# Sheet1.net
KiCad netlist of a schematic drawn in Altium Designer
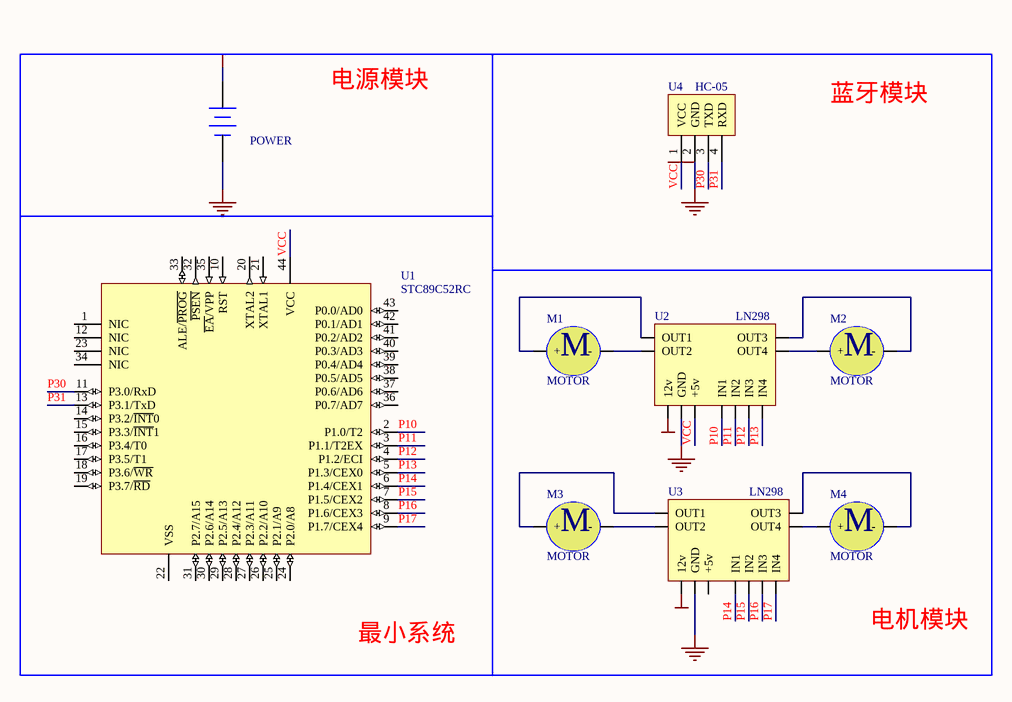
[diagram p0: Sheet1.SchDoc]

(export (version "E")
  (design (tool "Eeschema 10.0.6"))
  (components
    (comp (ref "M1") (value "MOTOR") (libsource (lib "MySchlib1") (part "MOTOR")))
    (comp (ref "M2") (value "MOTOR") (libsource (lib "MySchlib1") (part "MOTOR")))
    (comp (ref "M3") (value "MOTOR") (libsource (lib "MySchlib1") (part "MOTOR")))
    (comp (ref "M4") (value "MOTOR") (libsource (lib "MySchlib1") (part "MOTOR")))
    (comp (ref "POWER") (value "~") (footprint "NKBATTERY") (libsource (lib "*") (part "BATTERY")))
    (comp (ref "U1")
      (value "STC89C52RC")
      (footprint "SOT187-2")
      (description "80C51 8-Bit Flash Microcontroller Family, 8 kB ISP/IAP Flash with 512 B RAM.")
      (fields (field (name "PUBLISHER") "Altium Limited"))
      (libsource (lib "Philips Microcontroller 8-Bit") (part "P89C51RA2BA/01"))
    )
    (comp (ref "U2") (value "LN298") (libsource (lib "MySchlib1") (part "LN298")))
    (comp (ref "U3") (value "LN298") (libsource (lib "*") (part "LN298")))
    (comp (ref "U4") (value "HC-05") (libsource (lib "*") (part "HC-05")))
  )
  (nets
    (net (code "1") (name "/P10") (class "Default")
      (node (ref "U1") (pin "2") (pinfunction "P1.0/T2_2") (pintype "bidirectional"))
      (node (ref "U2") (pin "7") (pinfunction "IN1_7") (pintype "passive"))
    )
    (net (code "2") (name "/P11") (class "Default")
      (node (ref "U1") (pin "3") (pinfunction "P1.1/T2EX_3") (pintype "bidirectional"))
      (node (ref "U2") (pin "8") (pinfunction "IN2_8") (pintype "passive"))
    )
    (net (code "3") (name "/P12") (class "Default")
      (node (ref "U1") (pin "4") (pinfunction "P1.2/ECI_4") (pintype "bidirectional"))
      (node (ref "U2") (pin "9") (pinfunction "IN3_9") (pintype "passive"))
    )
    (net (code "4") (name "/P13") (class "Default")
      (node (ref "U1") (pin "5") (pinfunction "P1.3/CEX0_5") (pintype "bidirectional"))
      (node (ref "U2") (pin "10") (pinfunction "IN4_10") (pintype "passive"))
    )
    (net (code "5") (name "/P14") (class "Default")
      (node (ref "U1") (pin "6") (pinfunction "P1.4/CEX1_6") (pintype "bidirectional"))
      (node (ref "U3") (pin "7") (pinfunction "IN1_7") (pintype "passive"))
    )
    (net (code "6") (name "/P15") (class "Default")
      (node (ref "U1") (pin "7") (pinfunction "P1.5/CEX2_7") (pintype "bidirectional"))
      (node (ref "U3") (pin "8") (pinfunction "IN2_8") (pintype "passive"))
    )
    (net (code "7") (name "/P16") (class "Default")
      (node (ref "U1") (pin "8") (pinfunction "P1.6/CEX3_8") (pintype "bidirectional"))
      (node (ref "U3") (pin "9") (pinfunction "IN3_9") (pintype "passive"))
    )
    (net (code "8") (name "/P17") (class "Default")
      (node (ref "U1") (pin "9") (pinfunction "P1.7/CEX4_9") (pintype "bidirectional"))
      (node (ref "U3") (pin "10") (pinfunction "IN4_10") (pintype "passive"))
    )
    (net (code "9") (name "/P30") (class "Default")
      (node (ref "U1") (pin "11") (pinfunction "P3.0/RxD_11") (pintype "bidirectional"))
      (node (ref "U4") (pin "3") (pinfunction "TXD_3") (pintype "passive"))
    )
    (net (code "10") (name "/P31") (class "Default")
      (node (ref "U1") (pin "13") (pinfunction "P3.1/TxD_13") (pintype "bidirectional"))
      (node (ref "U4") (pin "4") (pinfunction "RXD_4") (pintype "passive"))
    )
    (net (code "11") (name "/VCC") (class "Default")
      (node (ref "U1") (pin "44") (pinfunction "VCC_44") (pintype "power_in"))
      (node (ref "U2") (pin "6") (pinfunction "+5v_6") (pintype "passive"))
      (node (ref "U4") (pin "1") (pinfunction "VCC_1") (pintype "passive"))
    )
    (net (code "12") (name "12V") (class "Default")
      (node (ref "POWER") (pin "1") (pinfunction "+_1") (pintype "passive"))
      (node (ref "U2") (pin "4") (pinfunction "12v_4") (pintype "passive"))
      (node (ref "U3") (pin "4") (pinfunction "12v_4") (pintype "passive"))
    )
    (net (code "13") (name "GND") (class "Default")
      (node (ref "U2") (pin "5") (pinfunction "GND_5") (pintype "passive"))
      (node (ref "U3") (pin "5") (pinfunction "GND_5") (pintype "passive"))
      (node (ref "U4") (pin "2") (pinfunction "GND_2") (pintype "passive"))
    )
    (net (code "14") (name "Net-(M1-+)") (class "Default")
      (node (ref "M1") (pin "0") (pinfunction "+_0") (pintype "passive"))
      (node (ref "U2") (pin "0") (pinfunction "OUT1_0") (pintype "passive"))
    )
    (net (code "15") (name "Net-(M1--)") (class "Default")
      (node (ref "M1") (pin "1") (pinfunction "-_1") (pintype "passive"))
      (node (ref "U2") (pin "1") (pinfunction "OUT2_1") (pintype "passive"))
    )
    (net (code "16") (name "Net-(M2-+)") (class "Default")
      (node (ref "M2") (pin "0") (pinfunction "+_0") (pintype "passive"))
      (node (ref "U2") (pin "3") (pinfunction "OUT4_3") (pintype "passive"))
    )
    (net (code "17") (name "Net-(M2--)") (class "Default")
      (node (ref "M2") (pin "1") (pinfunction "-_1") (pintype "passive"))
      (node (ref "U2") (pin "2") (pinfunction "OUT3_2") (pintype "passive"))
    )
    (net (code "18") (name "Net-(M3-+)") (class "Default")
      (node (ref "M3") (pin "0") (pinfunction "+_0") (pintype "passive"))
      (node (ref "U3") (pin "0") (pinfunction "OUT1_0") (pintype "passive"))
    )
    (net (code "19") (name "Net-(M3--)") (class "Default")
      (node (ref "M3") (pin "1") (pinfunction "-_1") (pintype "passive"))
      (node (ref "U3") (pin "1") (pinfunction "OUT2_1") (pintype "passive"))
    )
    (net (code "20") (name "Net-(M4-+)") (class "Default")
      (node (ref "M4") (pin "0") (pinfunction "+_0") (pintype "passive"))
      (node (ref "U3") (pin "3") (pinfunction "OUT4_3") (pintype "passive"))
    )
    (net (code "21") (name "Net-(M4--)") (class "Default")
      (node (ref "M4") (pin "1") (pinfunction "-_1") (pintype "passive"))
      (node (ref "U3") (pin "2") (pinfunction "OUT3_2") (pintype "passive"))
    )
    (net (code "22") (name "unconnected-(POWER-+-Pad2)") (class "Default")
      (node (ref "POWER") (pin "2") (pinfunction "+_2") (pintype "passive"))
    )
    (net (code "23") (name "unconnected-(U1-ALE{slash}~{PROG}-Pad33)") (class "Default")
      (node (ref "U1") (pin "33") (pinfunction "ALE/~{PROG}_33") (pintype "bidirectional"))
    )
    (net (code "24") (name "unconnected-(U1-NIC-Pad1)") (class "Default")
      (node (ref "U1") (pin "1") (pinfunction "NIC_1") (pintype "passive"))
    )
    (net (code "25") (name "unconnected-(U1-NIC-Pad12)") (class "Default")
      (node (ref "U1") (pin "12") (pinfunction "NIC_12") (pintype "passive"))
    )
    (net (code "26") (name "unconnected-(U1-NIC-Pad23)") (class "Default")
      (node (ref "U1") (pin "23") (pinfunction "NIC_23") (pintype "passive"))
    )
    (net (code "27") (name "unconnected-(U1-NIC-Pad34)") (class "Default")
      (node (ref "U1") (pin "34") (pinfunction "NIC_34") (pintype "passive"))
    )
    (net (code "28") (name "unconnected-(U1-P0.0{slash}AD0-Pad43)") (class "Default")
      (node (ref "U1") (pin "43") (pinfunction "P0.0/AD0_43") (pintype "bidirectional"))
    )
    (net (code "29") (name "unconnected-(U1-P0.1{slash}AD1-Pad42)") (class "Default")
      (node (ref "U1") (pin "42") (pinfunction "P0.1/AD1_42") (pintype "bidirectional"))
    )
    (net (code "30") (name "unconnected-(U1-P0.2{slash}AD2-Pad41)") (class "Default")
      (node (ref "U1") (pin "41") (pinfunction "P0.2/AD2_41") (pintype "bidirectional"))
    )
    (net (code "31") (name "unconnected-(U1-P0.3{slash}AD3-Pad40)") (class "Default")
      (node (ref "U1") (pin "40") (pinfunction "P0.3/AD3_40") (pintype "bidirectional"))
    )
    (net (code "32") (name "unconnected-(U1-P0.4{slash}AD4-Pad39)") (class "Default")
      (node (ref "U1") (pin "39") (pinfunction "P0.4/AD4_39") (pintype "bidirectional"))
    )
    (net (code "33") (name "unconnected-(U1-P0.5{slash}AD5-Pad38)") (class "Default")
      (node (ref "U1") (pin "38") (pinfunction "P0.5/AD5_38") (pintype "bidirectional"))
    )
    (net (code "34") (name "unconnected-(U1-P0.6{slash}AD6-Pad37)") (class "Default")
      (node (ref "U1") (pin "37") (pinfunction "P0.6/AD6_37") (pintype "bidirectional"))
    )
    (net (code "35") (name "unconnected-(U1-P0.7{slash}AD7-Pad36)") (class "Default")
      (node (ref "U1") (pin "36") (pinfunction "P0.7/AD7_36") (pintype "bidirectional"))
    )
    (net (code "36") (name "unconnected-(U1-P2.0{slash}A8-Pad24)") (class "Default")
      (node (ref "U1") (pin "24") (pinfunction "P2.0/A8_24") (pintype "bidirectional"))
    )
    (net (code "37") (name "unconnected-(U1-P2.1{slash}A9-Pad25)") (class "Default")
      (node (ref "U1") (pin "25") (pinfunction "P2.1/A9_25") (pintype "bidirectional"))
    )
    (net (code "38") (name "unconnected-(U1-P2.2{slash}A10-Pad26)") (class "Default")
      (node (ref "U1") (pin "26") (pinfunction "P2.2/A10_26") (pintype "bidirectional"))
    )
    (net (code "39") (name "unconnected-(U1-P2.3{slash}A11-Pad27)") (class "Default")
      (node (ref "U1") (pin "27") (pinfunction "P2.3/A11_27") (pintype "bidirectional"))
    )
    (net (code "40") (name "unconnected-(U1-P2.4{slash}A12-Pad28)") (class "Default")
      (node (ref "U1") (pin "28") (pinfunction "P2.4/A12_28") (pintype "bidirectional"))
    )
    (net (code "41") (name "unconnected-(U1-P2.5{slash}A13-Pad29)") (class "Default")
      (node (ref "U1") (pin "29") (pinfunction "P2.5/A13_29") (pintype "bidirectional"))
    )
    (net (code "42") (name "unconnected-(U1-P2.6{slash}A14-Pad30)") (class "Default")
      (node (ref "U1") (pin "30") (pinfunction "P2.6/A14_30") (pintype "bidirectional"))
    )
    (net (code "43") (name "unconnected-(U1-P2.7{slash}A15-Pad31)") (class "Default")
      (node (ref "U1") (pin "31") (pinfunction "P2.7/A15_31") (pintype "bidirectional"))
    )
    (net (code "44") (name "unconnected-(U1-P3.2{slash}~{INT}0-Pad14)") (class "Default")
      (node (ref "U1") (pin "14") (pinfunction "P3.2/~{INT}0_14") (pintype "bidirectional"))
    )
    (net (code "45") (name "unconnected-(U1-P3.3{slash}~{INT}1-Pad15)") (class "Default")
      (node (ref "U1") (pin "15") (pinfunction "P3.3/~{INT}1_15") (pintype "bidirectional"))
    )
    (net (code "46") (name "unconnected-(U1-P3.4{slash}T0-Pad16)") (class "Default")
      (node (ref "U1") (pin "16") (pinfunction "P3.4/T0_16") (pintype "bidirectional"))
    )
    (net (code "47") (name "unconnected-(U1-P3.5{slash}T1-Pad17)") (class "Default")
      (node (ref "U1") (pin "17") (pinfunction "P3.5/T1_17") (pintype "bidirectional"))
    )
    (net (code "48") (name "unconnected-(U1-P3.6{slash}~{WR}-Pad18)") (class "Default")
      (node (ref "U1") (pin "18") (pinfunction "P3.6/~{WR}_18") (pintype "bidirectional"))
    )
    (net (code "49") (name "unconnected-(U1-P3.7{slash}~{RD}-Pad19)") (class "Default")
      (node (ref "U1") (pin "19") (pinfunction "P3.7/~{RD}_19") (pintype "bidirectional"))
    )
    (net (code "50") (name "unconnected-(U1-RST-Pad10)") (class "Default")
      (node (ref "U1") (pin "10") (pinfunction "RST_10") (pintype "input"))
    )
    (net (code "51") (name "unconnected-(U1-VSS-Pad22)") (class "Default")
      (node (ref "U1") (pin "22") (pinfunction "VSS_22") (pintype "power_in"))
    )
    (net (code "52") (name "unconnected-(U1-XTAL1-Pad21)") (class "Default")
      (node (ref "U1") (pin "21") (pinfunction "XTAL1_21") (pintype "input"))
    )
    (net (code "53") (name "unconnected-(U1-XTAL2-Pad20)") (class "Default")
      (node (ref "U1") (pin "20") (pinfunction "XTAL2_20") (pintype "output"))
    )
    (net (code "54") (name "unconnected-(U1-~{EA}{slash}VPP-Pad35)") (class "Default")
      (node (ref "U1") (pin "35") (pinfunction "~{EA}/VPP_35") (pintype "input"))
    )
    (net (code "55") (name "unconnected-(U1-~{PSEN}-Pad32)") (class "Default")
      (node (ref "U1") (pin "32") (pinfunction "~{PSEN}_32") (pintype "output"))
    )
    (net (code "56") (name "unconnected-(U3-+5v-Pad6)") (class "Default")
      (node (ref "U3") (pin "6") (pinfunction "+5v_6") (pintype "passive"))
    )
  )
)
